# toilet_auto.net
KiCad netlist of a schematic drawn in EAGLE
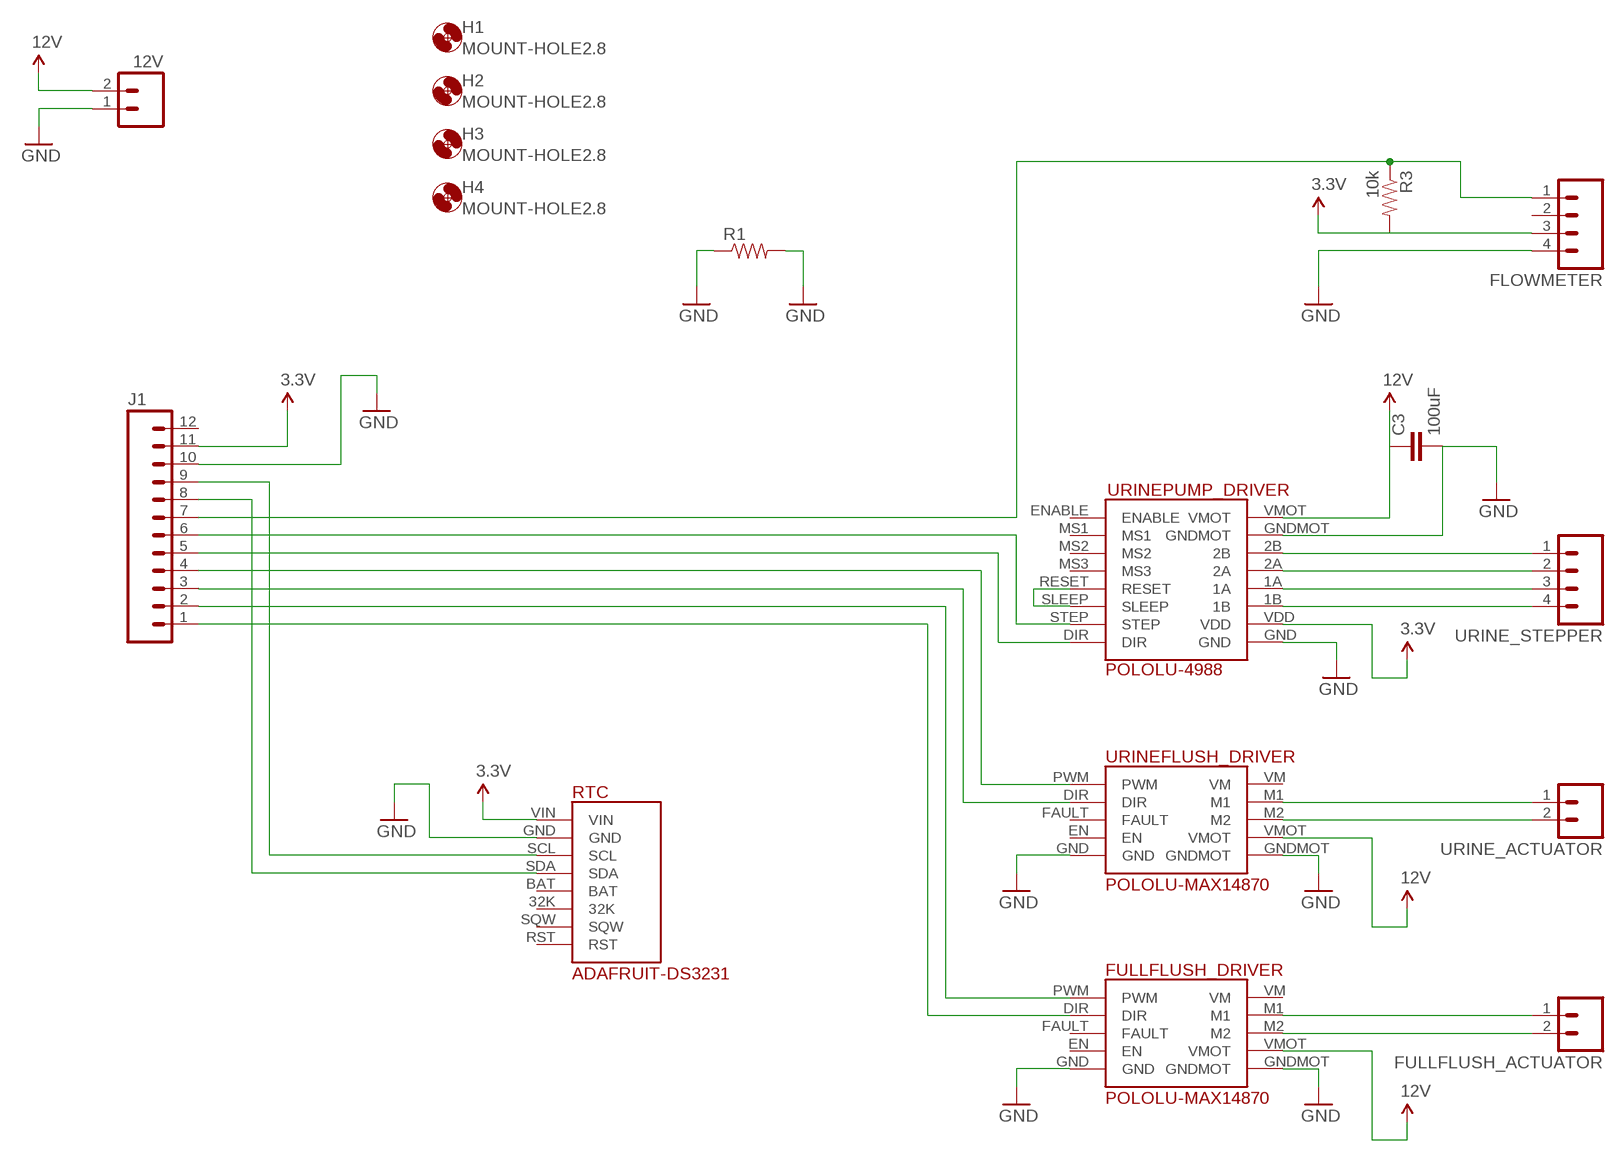
[diagram p0: schematic, sheet 1]

(export (version "E")
  (design (tool "Eeschema 10.0.6"))
  (components
    (comp (ref "12V")
      (value "M02LOCK_LONGPADS")
      (footprint "eagle-import:1X02_LOCK_LONGPADS")
      (libsource (lib "eagle-import") (part "M02LOCK_LONGPADS"))
    )
    (comp (ref "C3")
      (value "100uF")
      (footprint "eagle-import:CAP-PTH-SMALL-KIT")
      (libsource (lib "eagle-import") (part "0.1UF-50V-20%(PTH)KIT-EZ"))
    )
    (comp (ref "FLOWMETER")
      (value "M04LOCK_LONGPADS")
      (footprint "eagle-import:1X04_LOCK_LONGPADS")
      (libsource (lib "eagle-import") (part "M04LOCK_LONGPADS"))
    )
    (comp (ref "FULLFLUSH_ACTUATOR")
      (value "M02LOCK_LONGPADS")
      (footprint "eagle-import:1X02_LOCK_LONGPADS")
      (libsource (lib "eagle-import") (part "M02LOCK_LONGPADS"))
    )
    (comp (ref "FULLFLUSH_DRIVER")
      (value "POLOLU-MAX14870")
      (footprint "eagle-import:POLOLU-MAX14870")
      (libsource (lib "eagle-import") (part "POLOLU-MAX14870"))
    )
    (comp (ref "H1")
      (value "MOUNT-HOLE2.8")
      (footprint "eagle-import:2,8")
      (libsource (lib "eagle-import") (part "MOUNT-HOLE2.8"))
    )
    (comp (ref "H2")
      (value "MOUNT-HOLE2.8")
      (footprint "eagle-import:2,8")
      (libsource (lib "eagle-import") (part "MOUNT-HOLE2.8"))
    )
    (comp (ref "H3")
      (value "MOUNT-HOLE2.8")
      (footprint "eagle-import:2,8")
      (libsource (lib "eagle-import") (part "MOUNT-HOLE2.8"))
    )
    (comp (ref "H4")
      (value "MOUNT-HOLE2.8")
      (footprint "eagle-import:2,8")
      (libsource (lib "eagle-import") (part "MOUNT-HOLE2.8"))
    )
    (comp (ref "J1")
      (value "M12LOCK_LONGPADS")
      (footprint "eagle-import:1X12_LOCK_LONGPADS")
      (libsource (lib "eagle-import") (part "M12LOCK_LONGPADS"))
    )
    (comp (ref "R1")
      (value "RESISTORPTH-1/2W")
      (footprint "eagle-import:AXIAL-0.5")
      (libsource (lib "eagle-import") (part "SparkFun-Resistors_RESISTORPTH-1/2W"))
    )
    (comp (ref "R3")
      (value "10k")
      (footprint "eagle-import:AXIAL-0.3EZ")
      (libsource (lib "eagle-import") (part "RESISTOREZ"))
    )
    (comp (ref "RTC")
      (value "ADAFRUIT-DS3231")
      (footprint "eagle-import:ADAFRUIT-DS3231")
      (libsource (lib "eagle-import") (part "ADAFRUIT-DS3231"))
    )
    (comp (ref "URINEFLUSH_DRIVER")
      (value "POLOLU-MAX14870")
      (footprint "eagle-import:POLOLU-MAX14870")
      (libsource (lib "eagle-import") (part "POLOLU-MAX14870"))
    )
    (comp (ref "URINEPUMP_DRIVER")
      (value "POLOLU-4988")
      (footprint "eagle-import:POLOLU-4988")
      (libsource (lib "eagle-import") (part "POLOLU-4988"))
    )
    (comp (ref "URINE_ACTUATOR")
      (value "M02LOCK_LONGPADS")
      (footprint "eagle-import:1X02_LOCK_LONGPADS")
      (libsource (lib "eagle-import") (part "M02LOCK_LONGPADS"))
    )
    (comp (ref "URINE_STEPPER")
      (value "M04LOCK_LONGPADS")
      (footprint "eagle-import:1X04_LOCK_LONGPADS")
      (libsource (lib "eagle-import") (part "M04LOCK_LONGPADS"))
    )
  )
  (nets
    (net (code "1") (name "3.3V") (class "Default")
      (node (ref "FLOWMETER") (pin "3") (pinfunction "3_3") (pintype "passive"))
      (node (ref "J1") (pin "11") (pinfunction "11_11") (pintype "passive"))
      (node (ref "R3") (pin "P$2") (pinfunction "2_P$2") (pintype "passive"))
      (node (ref "RTC") (pin "VIN") (pinfunction "VIN_VIN") (pintype "bidirectional"))
      (node (ref "URINEPUMP_DRIVER") (pin "VDD") (pinfunction "VDD_VDD") (pintype "bidirectional"))
    )
    (net (code "2") (name "12V") (class "Default")
      (node (ref "12V") (pin "2") (pinfunction "2_2") (pintype "passive"))
      (node (ref "C3") (pin "1") (pinfunction "1_1") (pintype "passive"))
      (node (ref "FULLFLUSH_DRIVER") (pin "VMOT") (pinfunction "VMOT_VMOT") (pintype "bidirectional"))
      (node (ref "URINEFLUSH_DRIVER") (pin "VMOT") (pinfunction "VMOT_VMOT") (pintype "bidirectional"))
      (node (ref "URINEPUMP_DRIVER") (pin "VMOT") (pinfunction "VMOT_VMOT") (pintype "bidirectional"))
    )
    (net (code "3") (name "GND") (class "Default")
      (node (ref "12V") (pin "1") (pinfunction "1_1") (pintype "passive"))
      (node (ref "C3") (pin "2") (pinfunction "2_2") (pintype "passive"))
      (node (ref "FLOWMETER") (pin "4") (pinfunction "4_4") (pintype "passive"))
      (node (ref "FULLFLUSH_DRIVER") (pin "GND") (pinfunction "GND_GND") (pintype "bidirectional"))
      (node (ref "FULLFLUSH_DRIVER") (pin "GNDMOT") (pinfunction "GNDMOT_GNDMOT") (pintype "bidirectional"))
      (node (ref "J1") (pin "10") (pinfunction "10_10") (pintype "passive"))
      (node (ref "R1") (pin "P$1") (pinfunction "1_P$1") (pintype "passive"))
      (node (ref "R1") (pin "P$2") (pinfunction "2_P$2") (pintype "passive"))
      (node (ref "RTC") (pin "GND") (pinfunction "GND_GND") (pintype "bidirectional"))
      (node (ref "URINEFLUSH_DRIVER") (pin "GND") (pinfunction "GND_GND") (pintype "bidirectional"))
      (node (ref "URINEFLUSH_DRIVER") (pin "GNDMOT") (pinfunction "GNDMOT_GNDMOT") (pintype "bidirectional"))
      (node (ref "URINEPUMP_DRIVER") (pin "GND") (pinfunction "GND_GND") (pintype "bidirectional"))
      (node (ref "URINEPUMP_DRIVER") (pin "GNDMOT") (pinfunction "GNDMOT_GNDMOT") (pintype "bidirectional"))
    )
    (net (code "4") (name "Net-(FULLFLUSH_ACTUATOR-Pad1)") (class "Default")
      (node (ref "FULLFLUSH_ACTUATOR") (pin "1") (pinfunction "1_1") (pintype "passive"))
      (node (ref "FULLFLUSH_DRIVER") (pin "M1") (pinfunction "M1_M1") (pintype "bidirectional"))
    )
    (net (code "5") (name "Net-(FULLFLUSH_ACTUATOR-Pad2)") (class "Default")
      (node (ref "FULLFLUSH_ACTUATOR") (pin "2") (pinfunction "2_2") (pintype "passive"))
      (node (ref "FULLFLUSH_DRIVER") (pin "M2") (pinfunction "M2_M2") (pintype "bidirectional"))
    )
    (net (code "6") (name "Net-(FULLFLUSH_DRIVER-PadDIR)") (class "Default")
      (node (ref "FULLFLUSH_DRIVER") (pin "DIR") (pinfunction "DIR_DIR") (pintype "bidirectional"))
      (node (ref "J1") (pin "1") (pinfunction "1_1") (pintype "passive"))
    )
    (net (code "7") (name "Net-(FULLFLUSH_DRIVER-PadPWM)") (class "Default")
      (node (ref "FULLFLUSH_DRIVER") (pin "PWM") (pinfunction "PWM_PWM") (pintype "bidirectional"))
      (node (ref "J1") (pin "2") (pinfunction "2_2") (pintype "passive"))
    )
    (net (code "8") (name "Net-(J1-Pad3)") (class "Default")
      (node (ref "J1") (pin "3") (pinfunction "3_3") (pintype "passive"))
      (node (ref "URINEFLUSH_DRIVER") (pin "DIR") (pinfunction "DIR_DIR") (pintype "bidirectional"))
    )
    (net (code "9") (name "Net-(J1-Pad4)") (class "Default")
      (node (ref "J1") (pin "4") (pinfunction "4_4") (pintype "passive"))
      (node (ref "URINEFLUSH_DRIVER") (pin "PWM") (pinfunction "PWM_PWM") (pintype "bidirectional"))
    )
    (net (code "10") (name "Net-(J1-Pad5)") (class "Default")
      (node (ref "J1") (pin "5") (pinfunction "5_5") (pintype "passive"))
      (node (ref "URINEPUMP_DRIVER") (pin "DIR") (pinfunction "DIR_DIR") (pintype "bidirectional"))
    )
    (net (code "11") (name "Net-(J1-Pad6)") (class "Default")
      (node (ref "J1") (pin "6") (pinfunction "6_6") (pintype "passive"))
      (node (ref "URINEPUMP_DRIVER") (pin "STEP") (pinfunction "STEP_STEP") (pintype "bidirectional"))
    )
    (net (code "12") (name "Net-(J1-Pad8)") (class "Default")
      (node (ref "J1") (pin "8") (pinfunction "8_8") (pintype "passive"))
      (node (ref "RTC") (pin "SDA") (pinfunction "SDA_SDA") (pintype "bidirectional"))
    )
    (net (code "13") (name "Net-(J1-Pad9)") (class "Default")
      (node (ref "J1") (pin "9") (pinfunction "9_9") (pintype "passive"))
      (node (ref "RTC") (pin "SCL") (pinfunction "SCL_SCL") (pintype "bidirectional"))
    )
    (net (code "14") (name "Net-(R3-1)") (class "Default")
      (node (ref "FLOWMETER") (pin "1") (pinfunction "1_1") (pintype "passive"))
      (node (ref "J1") (pin "7") (pinfunction "7_7") (pintype "passive"))
      (node (ref "R3") (pin "P$1") (pinfunction "1_P$1") (pintype "passive"))
    )
    (net (code "15") (name "Net-(URINEFLUSH_DRIVER-PadM1)") (class "Default")
      (node (ref "URINEFLUSH_DRIVER") (pin "M1") (pinfunction "M1_M1") (pintype "bidirectional"))
      (node (ref "URINE_ACTUATOR") (pin "1") (pinfunction "1_1") (pintype "passive"))
    )
    (net (code "16") (name "Net-(URINEFLUSH_DRIVER-PadM2)") (class "Default")
      (node (ref "URINEFLUSH_DRIVER") (pin "M2") (pinfunction "M2_M2") (pintype "bidirectional"))
      (node (ref "URINE_ACTUATOR") (pin "2") (pinfunction "2_2") (pintype "passive"))
    )
    (net (code "17") (name "Net-(URINEPUMP_DRIVER-Pad1A)") (class "Default")
      (node (ref "URINEPUMP_DRIVER") (pin "1A") (pinfunction "1A_1A") (pintype "bidirectional"))
      (node (ref "URINE_STEPPER") (pin "3") (pinfunction "3_3") (pintype "passive"))
    )
    (net (code "18") (name "Net-(URINEPUMP_DRIVER-Pad1B)") (class "Default")
      (node (ref "URINEPUMP_DRIVER") (pin "1B") (pinfunction "1B_1B") (pintype "bidirectional"))
      (node (ref "URINE_STEPPER") (pin "4") (pinfunction "4_4") (pintype "passive"))
    )
    (net (code "19") (name "Net-(URINEPUMP_DRIVER-Pad2A)") (class "Default")
      (node (ref "URINEPUMP_DRIVER") (pin "2A") (pinfunction "2A_2A") (pintype "bidirectional"))
      (node (ref "URINE_STEPPER") (pin "2") (pinfunction "2_2") (pintype "passive"))
    )
    (net (code "20") (name "Net-(URINEPUMP_DRIVER-Pad2B)") (class "Default")
      (node (ref "URINEPUMP_DRIVER") (pin "2B") (pinfunction "2B_2B") (pintype "bidirectional"))
      (node (ref "URINE_STEPPER") (pin "1") (pinfunction "1_1") (pintype "passive"))
    )
    (net (code "21") (name "Net-(URINEPUMP_DRIVER-PadRESET)") (class "Default")
      (node (ref "URINEPUMP_DRIVER") (pin "RESET") (pinfunction "RESET_RESET") (pintype "bidirectional"))
      (node (ref "URINEPUMP_DRIVER") (pin "SLEEP") (pinfunction "SLEEP_SLEEP") (pintype "bidirectional"))
    )
    (net (code "22") (name "unconnected-(FLOWMETER-Pad2)") (class "Default")
      (node (ref "FLOWMETER") (pin "2") (pinfunction "2_2") (pintype "passive"))
    )
    (net (code "23") (name "unconnected-(FULLFLUSH_DRIVER-PadEN)") (class "Default")
      (node (ref "FULLFLUSH_DRIVER") (pin "EN") (pinfunction "EN_EN") (pintype "bidirectional"))
    )
    (net (code "24") (name "unconnected-(FULLFLUSH_DRIVER-PadFAULT)") (class "Default")
      (node (ref "FULLFLUSH_DRIVER") (pin "FAULT") (pinfunction "FAULT_FAULT") (pintype "bidirectional"))
    )
    (net (code "25") (name "unconnected-(FULLFLUSH_DRIVER-PadVM)") (class "Default")
      (node (ref "FULLFLUSH_DRIVER") (pin "VM") (pinfunction "VM_VM") (pintype "bidirectional"))
    )
    (net (code "26") (name "unconnected-(J1-Pad12)") (class "Default")
      (node (ref "J1") (pin "12") (pinfunction "12_12") (pintype "passive"))
    )
    (net (code "27") (name "unconnected-(RTC-Pad32K)") (class "Default")
      (node (ref "RTC") (pin "32K") (pinfunction "32K_32K") (pintype "bidirectional"))
    )
    (net (code "28") (name "unconnected-(RTC-PadBAT)") (class "Default")
      (node (ref "RTC") (pin "BAT") (pinfunction "BAT_BAT") (pintype "bidirectional"))
    )
    (net (code "29") (name "unconnected-(RTC-PadRST)") (class "Default")
      (node (ref "RTC") (pin "RST") (pinfunction "RST_RST") (pintype "bidirectional"))
    )
    (net (code "30") (name "unconnected-(RTC-PadSQW)") (class "Default")
      (node (ref "RTC") (pin "SQW") (pinfunction "SQW_SQW") (pintype "bidirectional"))
    )
    (net (code "31") (name "unconnected-(URINEFLUSH_DRIVER-PadEN)") (class "Default")
      (node (ref "URINEFLUSH_DRIVER") (pin "EN") (pinfunction "EN_EN") (pintype "bidirectional"))
    )
    (net (code "32") (name "unconnected-(URINEFLUSH_DRIVER-PadFAULT)") (class "Default")
      (node (ref "URINEFLUSH_DRIVER") (pin "FAULT") (pinfunction "FAULT_FAULT") (pintype "bidirectional"))
    )
    (net (code "33") (name "unconnected-(URINEFLUSH_DRIVER-PadVM)") (class "Default")
      (node (ref "URINEFLUSH_DRIVER") (pin "VM") (pinfunction "VM_VM") (pintype "bidirectional"))
    )
    (net (code "34") (name "unconnected-(URINEPUMP_DRIVER-PadENABLE)") (class "Default")
      (node (ref "URINEPUMP_DRIVER") (pin "ENABLE") (pinfunction "ENABLE_ENABLE") (pintype "bidirectional"))
    )
    (net (code "35") (name "unconnected-(URINEPUMP_DRIVER-PadMS1)") (class "Default")
      (node (ref "URINEPUMP_DRIVER") (pin "MS1") (pinfunction "MS1_MS1") (pintype "bidirectional"))
    )
    (net (code "36") (name "unconnected-(URINEPUMP_DRIVER-PadMS2)") (class "Default")
      (node (ref "URINEPUMP_DRIVER") (pin "MS2") (pinfunction "MS2_MS2") (pintype "bidirectional"))
    )
    (net (code "37") (name "unconnected-(URINEPUMP_DRIVER-PadMS3)") (class "Default")
      (node (ref "URINEPUMP_DRIVER") (pin "MS3") (pinfunction "MS3_MS3") (pintype "bidirectional"))
    )
  )
)
